# 4WD_V1_0.net
KiCad netlist of a schematic drawn in Altium Designer
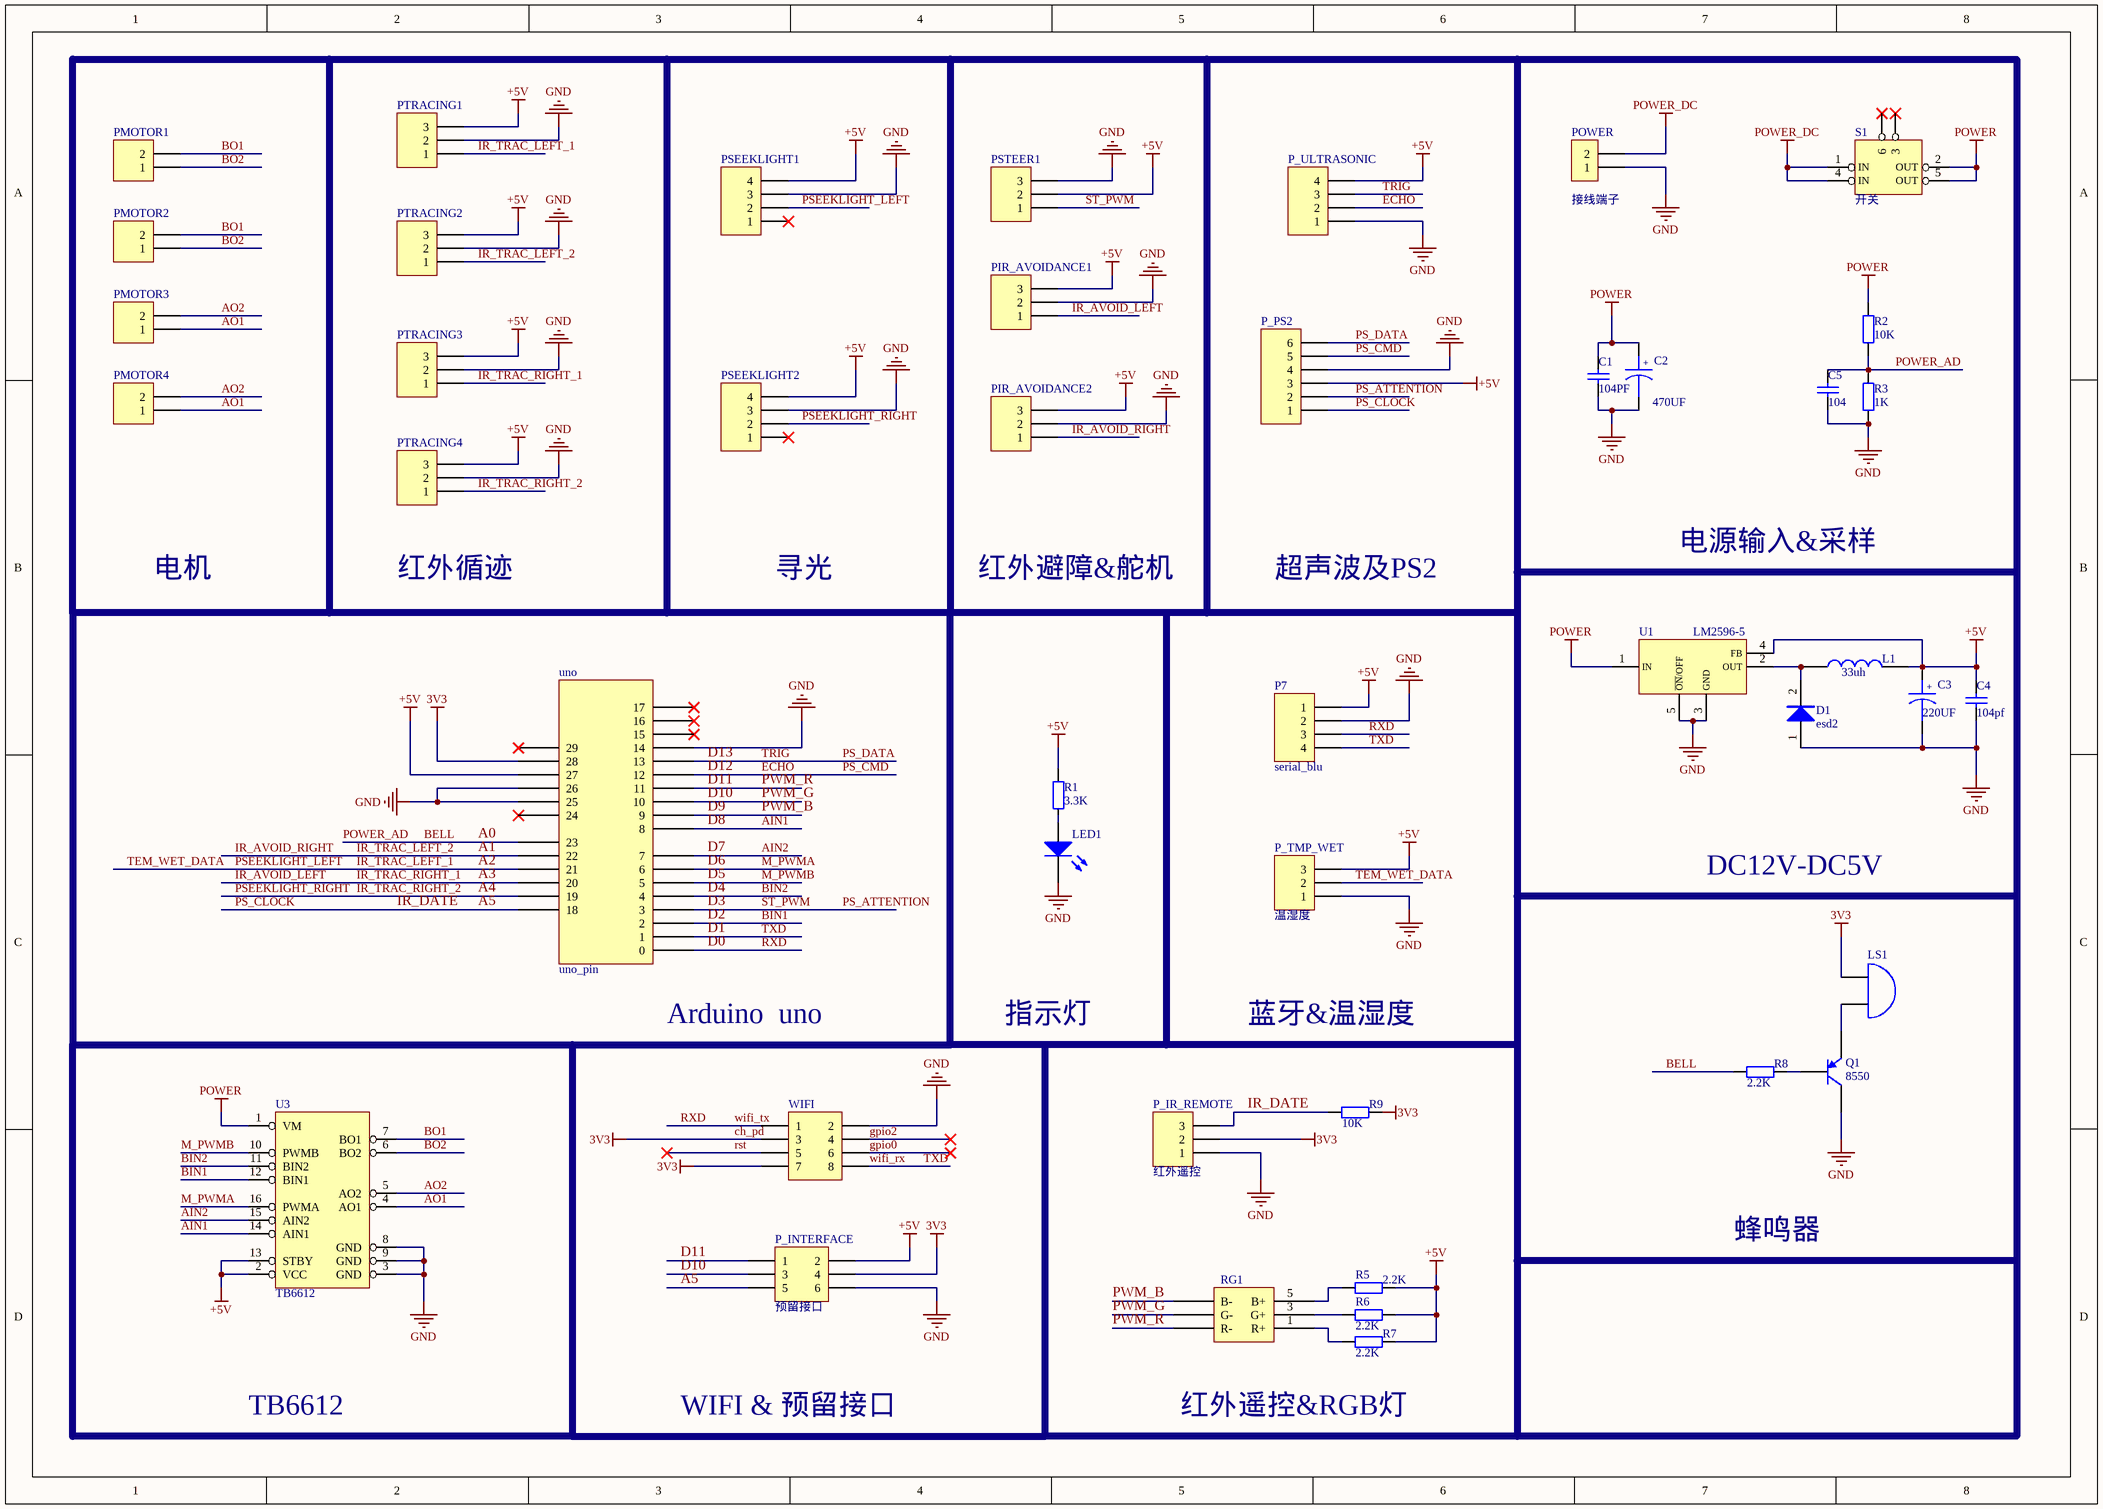
[diagram p0: 4WD_V1.0.SchDoc]

(export (version "E")
  (design (tool "Eeschema 10.0.6"))
  (components
    (comp (ref "C1")
      (value "Cap")
      (footprint "C 0603_L")
      (description "Capacitor")
      (fields (field (name "ALTIUM_UNNAMED_1") "104PF") (field (name "PUBLISHER") "Altium Limited"))
      (libsource (lib "balanceDriver") (part "Cap"))
    )
    (comp (ref "C2")
      (value "CAP4 电解电容")
      (footprint "CAP6.3")
      (description "Capacitor")
      (fields (field (name "ALTIUM_UNNAMED_1") "470UF"))
      (libsource (lib "double_wheel_ctrl") (part "CAP4 电解电容"))
    )
    (comp (ref "C3")
      (value "CAP4 电解电容")
      (footprint "CAP6.3")
      (description "Capacitor")
      (fields (field (name "ALTIUM_UNNAMED_1") "220UF"))
      (libsource (lib "double_wheel_ctrl") (part "CAP4 电解电容"))
    )
    (comp (ref "C4")
      (value "Cap")
      (footprint "C 0603_L")
      (description "Capacitor")
      (fields (field (name "ALTIUM_UNNAMED_1") "104pf") (field (name "PUBLISHER") "Altium Limited"))
      (libsource (lib "balanceDriver") (part "Cap"))
    )
    (comp (ref "C5")
      (value "104")
      (footprint "C 0603_L")
      (description "Capacitor")
      (fields (field (name "Comment") "Cap") (field (name "PUBLISHER") "Altium Limited"))
      (libsource (lib "Miscellaneous Devices") (part "Cap"))
    )
    (comp (ref "D1") (value "esd2") (footprint "SMA") (libsource (lib "double_wheel_ctrl") (part "DIODE2")))
    (comp (ref "L1")
      (value "INDUCTOR 0")
      (footprint "CDRH74")
      (fields (field (name "ALTIUM_UNNAMED_1") "33uh"))
      (libsource (lib "balanceDriver") (part "INDUCTOR 0"))
    )
    (comp (ref "LED1")
      (value "LED3")
      (footprint "LED 0603Y")
      (description "Typical RED, GREEN, YELLOW, AMBER GaAs LED")
      (fields (field (name "PUBLISHER") "Altium Limited"))
      (libsource (lib "Miscellaneous Devices") (part "LED2"))
    )
    (comp (ref "LS1")
      (value "Bell")
      (footprint "BEEP 5x9x5.5")
      (description "Electrical Bell")
      (fields (field (name "PUBLISHER") "Altium Limited"))
      (libsource (lib "Miscellaneous Devices") (part "Bell"))
    )
    (comp (ref "P7")
      (value "serial_blu")
      (footprint "HDR2.54-M-LI-4P")
      (description "Header, 4-Pin")
      (fields (field (name "PUBLISHER") "Altium Limited"))
      (libsource (lib "Miscellaneous Connectors") (part "Header 4"))
    )
    (comp (ref "PIR_AVOIDANCE1")
      (value "Header 3")
      (footprint "XH2.54-WI-3P")
      (description "Header, 3-Pin")
      (fields (field (name "PUBLISHER") "Altium Limited"))
      (libsource (lib "Miscellaneous Connectors") (part "Header 3"))
    )
    (comp (ref "PIR_AVOIDANCE2")
      (value "Header 3")
      (footprint "XH2.54-WI-3P")
      (description "Header, 3-Pin")
      (fields (field (name "PUBLISHER") "Altium Limited"))
      (libsource (lib "Miscellaneous Connectors") (part "Header 3"))
    )
    (comp (ref "PMOTOR1")
      (value "Header 2")
      (footprint "XH2.54-WI-2P")
      (description "Header, 2-Pin")
      (fields (field (name "PUBLISHER") "Altium Limited"))
      (libsource (lib "Miscellaneous Connectors") (part "Header 2"))
    )
    (comp (ref "PMOTOR2")
      (value "Header 2")
      (footprint "XH2.54-WI-2P")
      (description "Header, 2-Pin")
      (fields (field (name "PUBLISHER") "Altium Limited"))
      (libsource (lib "Miscellaneous Connectors") (part "Header 2"))
    )
    (comp (ref "PMOTOR3")
      (value "Header 2")
      (footprint "XH2.54-WI-2P")
      (description "Header, 2-Pin")
      (fields (field (name "PUBLISHER") "Altium Limited"))
      (libsource (lib "Miscellaneous Connectors") (part "Header 2"))
    )
    (comp (ref "PMOTOR4")
      (value "Header 2")
      (footprint "XH2.54-WI-2P")
      (description "Header, 2-Pin")
      (fields (field (name "PUBLISHER") "Altium Limited"))
      (libsource (lib "Miscellaneous Connectors") (part "Header 2"))
    )
    (comp (ref "POWER")
      (value "接线端子")
      (footprint "XH2.54-WI-2P")
      (libsource (lib "double_wheel_ctrl") (part "PIN2"))
    )
    (comp (ref "PSEEKLIGHT1")
      (value "Header 4")
      (footprint "XH2.54-WI-4P")
      (description "Header, 4-Pin")
      (fields (field (name "PUBLISHER") "Altium Limited"))
      (libsource (lib "") (part "Header 4_1"))
    )
    (comp (ref "PSEEKLIGHT2")
      (value "Header 4")
      (footprint "XH2.54-WI-4P")
      (description "Header, 4-Pin")
      (fields (field (name "PUBLISHER") "Altium Limited"))
      (libsource (lib "") (part "Header 4_1"))
    )
    (comp (ref "PSTEER1")
      (value "Header 3")
      (footprint "HDR2.54-WI-3P")
      (description "Header, 3-Pin")
      (fields (field (name "PUBLISHER") "Altium Limited"))
      (libsource (lib "Miscellaneous Connectors") (part "Header 3"))
    )
    (comp (ref "PTRACING1")
      (value "Header 3")
      (footprint "XH2.54-WI-3P")
      (description "Header, 3-Pin")
      (fields (field (name "PUBLISHER") "Altium Limited"))
      (libsource (lib "Miscellaneous Connectors") (part "Header 3"))
    )
    (comp (ref "PTRACING2")
      (value "Header 3")
      (footprint "XH2.54-WI-3P")
      (description "Header, 3-Pin")
      (fields (field (name "PUBLISHER") "Altium Limited"))
      (libsource (lib "Miscellaneous Connectors") (part "Header 3"))
    )
    (comp (ref "PTRACING3")
      (value "Header 3")
      (footprint "XH2.54-WI-3P")
      (description "Header, 3-Pin")
      (fields (field (name "PUBLISHER") "Altium Limited"))
      (libsource (lib "Miscellaneous Connectors") (part "Header 3"))
    )
    (comp (ref "PTRACING4")
      (value "Header 3")
      (footprint "XH2.54-WI-3P")
      (description "Header, 3-Pin")
      (fields (field (name "PUBLISHER") "Altium Limited"))
      (libsource (lib "Miscellaneous Connectors") (part "Header 3"))
    )
    (comp (ref "P_INTERFACE")
      (value "预留接口")
      (footprint "HDR2.54-LI-2x3P")
      (description "Header, 3-Pin, Dual row")
      (fields (field (name "PUBLISHER") "Altium Limited"))
      (libsource (lib "Miscellaneous Connectors") (part "Header 3X2"))
    )
    (comp (ref "P_IR_REMOTE")
      (value "红外遥控")
      (footprint "HDR2.54-M-LI-3P")
      (description "Header, 3-Pin")
      (fields (field (name "PUBLISHER") "Altium Limited"))
      (libsource (lib "Miscellaneous Connectors") (part "Header 3"))
    )
    (comp (ref "P_PS2")
      (value "Header 6")
      (footprint "HDR2.54-LI-6P")
      (description "Header, 6-Pin")
      (fields (field (name "PUBLISHER") "Altium Limited"))
      (libsource (lib "Miscellaneous Connectors") (part "Header 6"))
    )
    (comp (ref "P_TMP_WET")
      (value "温湿度")
      (footprint "HDR2.54-M-LI-3P")
      (description "Header, 3-Pin")
      (fields (field (name "PUBLISHER") "Altium Limited"))
      (libsource (lib "Miscellaneous Connectors") (part "Header 3"))
    )
    (comp (ref "P_ULTRASONIC")
      (value "Header 4")
      (footprint "HDR2.54-WI-4P")
      (description "Header, 4-Pin")
      (fields (field (name "PUBLISHER") "Altium Limited"))
      (libsource (lib "") (part "Header 4_1"))
    )
    (comp (ref "Q1")
      (value "8550")
      (footprint "SOT23-3L")
      (description "PNP General Purpose Amplifier")
      (fields (field (name "PUBLISHER") "Altium Limited"))
      (libsource (lib "4WD_ARDUINO_PCB_QINHE") (part "2N3906"))
    )
    (comp (ref "R1")
      (value "3.3K")
      (footprint "R 0603_L")
      (description "Resistor")
      (fields (field (name "Comment") "Res2") (field (name "PUBLISHER") "Altium Limited"))
      (libsource (lib "Miscellaneous Devices") (part "Res2"))
    )
    (comp (ref "R2")
      (value "10K")
      (footprint "R 0603_L")
      (description "Resistor")
      (fields (field (name "Comment") "Res2") (field (name "PUBLISHER") "Altium Limited"))
      (libsource (lib "Miscellaneous Devices") (part "Res2"))
    )
    (comp (ref "R3")
      (value "1K")
      (footprint "R 0603_L")
      (description "Resistor")
      (fields (field (name "Comment") "Res2") (field (name "PUBLISHER") "Altium Limited"))
      (libsource (lib "Miscellaneous Devices") (part "Res2"))
    )
    (comp (ref "R5")
      (value "2.2K")
      (footprint "R 0603_L")
      (description "Resistor")
      (fields (field (name "Comment") "Res2") (field (name "PUBLISHER") "Altium Limited"))
      (libsource (lib "") (part "Res2_1"))
    )
    (comp (ref "R6")
      (value "2.2K")
      (footprint "R 0603_L")
      (description "Resistor")
      (fields (field (name "Comment") "Res2") (field (name "PUBLISHER") "Altium Limited"))
      (libsource (lib "") (part "Res2_1"))
    )
    (comp (ref "R7")
      (value "2.2K")
      (footprint "R 0603_L")
      (description "Resistor")
      (fields (field (name "Comment") "Res2") (field (name "PUBLISHER") "Altium Limited"))
      (libsource (lib "") (part "Res2_1"))
    )
    (comp (ref "R8")
      (value "2.2K")
      (footprint "R 0603_L")
      (description "Resistor")
      (fields (field (name "Comment") "Res2") (field (name "PUBLISHER") "Altium Limited"))
      (libsource (lib "") (part "Res2_1"))
    )
    (comp (ref "R9")
      (value "10K")
      (footprint "R 0603_L")
      (description "Resistor")
      (fields (field (name "Comment") "Res2") (field (name "PUBLISHER") "Altium Limited"))
      (libsource (lib "") (part "Res2_1"))
    )
    (comp (ref "RG1")
      (value "RGB_LED_6")
      (footprint "LED 5050")
      (libsource (lib "RGB_PCB") (part "RGB_LED_6"))
    )
    (comp (ref "S1")
      (value "开关")
      (footprint "SWITCH_SELFLOCKING")
      (libsource (lib "double_wheel_ctrl") (part "switch"))
    )
    (comp (ref "U1")
      (value "LM2596-5")
      (footprint "TO263-5A")
      (libsource (lib "balanceDriver") (part "LM2560-5"))
    )
    (comp (ref "U3")
      (value "TB6612")
      (footprint "TB6612")
      (libsource (lib "double_wheel_ctrl") (part "TB6612"))
    )
    (comp (ref "uno") (value "uno_pin") (footprint "UNO_PIN") (libsource (lib "driver") (part "uno_pin")))
    (comp (ref "WIFI")
      (value "Header 4X2")
      (footprint "wifi")
      (description "Header, 4-Pin, Dual row")
      (fields (field (name "PUBLISHER") "Altium Limited"))
      (libsource (lib "Miscellaneous Connectors") (part "Header 4X2"))
    )
  )
  (nets
    (net (code "1") (name "+5V") (class "Default")
      (node (ref "C3") (pin "1") (pinfunction "1_1") (pintype "passive"))
      (node (ref "C4") (pin "2") (pinfunction "2_2") (pintype "passive"))
      (node (ref "L1") (pin "2") (pinfunction "2_2") (pintype "passive"))
      (node (ref "P7") (pin "1") (pinfunction "1_1") (pintype "passive"))
      (node (ref "PIR_AVOIDANCE1") (pin "3") (pinfunction "3_3") (pintype "passive"))
      (node (ref "PIR_AVOIDANCE2") (pin "3") (pinfunction "3_3") (pintype "passive"))
      (node (ref "PSEEKLIGHT1") (pin "4") (pinfunction "4_4") (pintype "passive"))
      (node (ref "PSEEKLIGHT2") (pin "4") (pinfunction "4_4") (pintype "passive"))
      (node (ref "PSTEER1") (pin "2") (pinfunction "2_2") (pintype "passive"))
      (node (ref "PTRACING1") (pin "3") (pinfunction "3_3") (pintype "passive"))
      (node (ref "PTRACING2") (pin "3") (pinfunction "3_3") (pintype "passive"))
      (node (ref "PTRACING3") (pin "3") (pinfunction "3_3") (pintype "passive"))
      (node (ref "PTRACING4") (pin "3") (pinfunction "3_3") (pintype "passive"))
      (node (ref "P_INTERFACE") (pin "2") (pinfunction "2_2") (pintype "passive"))
      (node (ref "P_PS2") (pin "3") (pinfunction "3_3") (pintype "passive"))
      (node (ref "P_TMP_WET") (pin "3") (pinfunction "3_3") (pintype "passive"))
      (node (ref "P_ULTRASONIC") (pin "4") (pinfunction "4_4") (pintype "passive"))
      (node (ref "R1") (pin "1") (pinfunction "1_1") (pintype "passive"))
      (node (ref "R5") (pin "1") (pinfunction "1_1") (pintype "passive"))
      (node (ref "R6") (pin "1") (pinfunction "1_1") (pintype "passive"))
      (node (ref "R7") (pin "1") (pinfunction "1_1") (pintype "passive"))
      (node (ref "U1") (pin "4") (pinfunction "FB_4") (pintype "passive"))
      (node (ref "U3") (pin "13") (pinfunction "STBY_13") (pintype "passive"))
      (node (ref "U3") (pin "2") (pinfunction "VCC_2") (pintype "passive"))
      (node (ref "uno") (pin "27") (pinfunction "27_27") (pintype "passive"))
    )
    (net (code "2") (name "/A0") (class "Default")
      (node (ref "C5") (pin "1") (pinfunction "1_1") (pintype "passive"))
      (node (ref "R2") (pin "2") (pinfunction "2_2") (pintype "passive"))
      (node (ref "R3") (pin "1") (pinfunction "1_1") (pintype "passive"))
      (node (ref "R8") (pin "2") (pinfunction "2_2") (pintype "passive"))
      (node (ref "uno") (pin "23") (pinfunction "23_23") (pintype "passive"))
    )
    (net (code "3") (name "/A1") (class "Default")
      (node (ref "PIR_AVOIDANCE2") (pin "1") (pinfunction "1_1") (pintype "passive"))
      (node (ref "PTRACING2") (pin "1") (pinfunction "1_1") (pintype "passive"))
      (node (ref "uno") (pin "22") (pinfunction "22_22") (pintype "passive"))
    )
    (net (code "4") (name "/A2") (class "Default")
      (node (ref "PSEEKLIGHT1") (pin "2") (pinfunction "2_2") (pintype "passive"))
      (node (ref "PTRACING1") (pin "1") (pinfunction "1_1") (pintype "passive"))
      (node (ref "P_TMP_WET") (pin "2") (pinfunction "2_2") (pintype "passive"))
      (node (ref "uno") (pin "21") (pinfunction "21_21") (pintype "passive"))
    )
    (net (code "5") (name "/A3") (class "Default")
      (node (ref "PIR_AVOIDANCE1") (pin "1") (pinfunction "1_1") (pintype "passive"))
      (node (ref "PTRACING3") (pin "1") (pinfunction "1_1") (pintype "passive"))
      (node (ref "uno") (pin "20") (pinfunction "20_20") (pintype "passive"))
    )
    (net (code "6") (name "/A4") (class "Default")
      (node (ref "PSEEKLIGHT2") (pin "2") (pinfunction "2_2") (pintype "passive"))
      (node (ref "PTRACING4") (pin "1") (pinfunction "1_1") (pintype "passive"))
      (node (ref "uno") (pin "19") (pinfunction "19_19") (pintype "passive"))
    )
    (net (code "7") (name "/A5") (class "Default")
      (node (ref "P_INTERFACE") (pin "5") (pinfunction "5_5") (pintype "passive"))
      (node (ref "P_IR_REMOTE") (pin "3") (pinfunction "3_3") (pintype "passive"))
      (node (ref "P_PS2") (pin "1") (pinfunction "1_1") (pintype "passive"))
      (node (ref "R9") (pin "2") (pinfunction "2_2") (pintype "passive"))
      (node (ref "uno") (pin "18") (pinfunction "18_18") (pintype "passive"))
    )
    (net (code "8") (name "/AIN1") (class "Default")
      (node (ref "U3") (pin "14") (pinfunction "AIN1_14") (pintype "passive"))
      (node (ref "uno") (pin "8") (pinfunction "8_8") (pintype "passive"))
    )
    (net (code "9") (name "/AIN2") (class "Default")
      (node (ref "U3") (pin "15") (pinfunction "AIN2_15") (pintype "passive"))
      (node (ref "uno") (pin "7") (pinfunction "7_7") (pintype "passive"))
    )
    (net (code "10") (name "/AO1") (class "Default")
      (node (ref "PMOTOR3") (pin "1") (pinfunction "1_1") (pintype "passive"))
      (node (ref "PMOTOR4") (pin "1") (pinfunction "1_1") (pintype "passive"))
      (node (ref "U3") (pin "4") (pinfunction "AO1_4") (pintype "passive"))
    )
    (net (code "11") (name "/AO2") (class "Default")
      (node (ref "PMOTOR3") (pin "2") (pinfunction "2_2") (pintype "passive"))
      (node (ref "PMOTOR4") (pin "2") (pinfunction "2_2") (pintype "passive"))
      (node (ref "U3") (pin "5") (pinfunction "AO2_5") (pintype "passive"))
    )
    (net (code "12") (name "/BIN1") (class "Default")
      (node (ref "U3") (pin "12") (pinfunction "BIN1_12") (pintype "passive"))
      (node (ref "uno") (pin "2") (pinfunction "2_2") (pintype "passive"))
    )
    (net (code "13") (name "/BIN2") (class "Default")
      (node (ref "U3") (pin "11") (pinfunction "BIN2_11") (pintype "passive"))
      (node (ref "uno") (pin "4") (pinfunction "4_4") (pintype "passive"))
    )
    (net (code "14") (name "/BO1") (class "Default")
      (node (ref "PMOTOR1") (pin "2") (pinfunction "2_2") (pintype "passive"))
      (node (ref "PMOTOR2") (pin "2") (pinfunction "2_2") (pintype "passive"))
      (node (ref "U3") (pin "7") (pinfunction "BO1_7") (pintype "passive"))
    )
    (net (code "15") (name "/BO2") (class "Default")
      (node (ref "PMOTOR1") (pin "1") (pinfunction "1_1") (pintype "passive"))
      (node (ref "PMOTOR2") (pin "1") (pinfunction "1_1") (pintype "passive"))
      (node (ref "U3") (pin "6") (pinfunction "BO2_6") (pintype "passive"))
    )
    (net (code "16") (name "/D0") (class "Default")
      (node (ref "P7") (pin "3") (pinfunction "3_3") (pintype "passive"))
      (node (ref "WIFI") (pin "1") (pinfunction "1_1") (pintype "passive"))
      (node (ref "uno") (pin "0") (pinfunction "0_0") (pintype "passive"))
    )
    (net (code "17") (name "/D1") (class "Default")
      (node (ref "P7") (pin "4") (pinfunction "4_4") (pintype "passive"))
      (node (ref "WIFI") (pin "8") (pinfunction "8_8") (pintype "passive"))
      (node (ref "uno") (pin "1") (pinfunction "1_1") (pintype "passive"))
    )
    (net (code "18") (name "/D3") (class "Default")
      (node (ref "PSTEER1") (pin "1") (pinfunction "1_1") (pintype "passive"))
      (node (ref "P_PS2") (pin "2") (pinfunction "2_2") (pintype "passive"))
      (node (ref "uno") (pin "3") (pinfunction "3_3") (pintype "passive"))
    )
    (net (code "19") (name "/D5") (class "Default")
      (node (ref "U3") (pin "10") (pinfunction "PWMB_10") (pintype "passive"))
      (node (ref "uno") (pin "5") (pinfunction "5_5") (pintype "passive"))
    )
    (net (code "20") (name "/D6") (class "Default")
      (node (ref "U3") (pin "16") (pinfunction "PWMA_16") (pintype "passive"))
      (node (ref "uno") (pin "6") (pinfunction "6_6") (pintype "passive"))
    )
    (net (code "21") (name "/D9") (class "Default")
      (node (ref "RG1") (pin "6") (pinfunction "B-_6") (pintype "power_in"))
      (node (ref "uno") (pin "9") (pinfunction "9_9") (pintype "passive"))
    )
    (net (code "22") (name "/D10") (class "Default")
      (node (ref "P_INTERFACE") (pin "3") (pinfunction "3_3") (pintype "passive"))
      (node (ref "RG1") (pin "4") (pinfunction "G-_4") (pintype "power_in"))
      (node (ref "uno") (pin "10") (pinfunction "10_10") (pintype "passive"))
    )
    (net (code "23") (name "/D11") (class "Default")
      (node (ref "P_INTERFACE") (pin "1") (pinfunction "1_1") (pintype "passive"))
      (node (ref "RG1") (pin "2") (pinfunction "R-_2") (pintype "power_in"))
      (node (ref "uno") (pin "11") (pinfunction "11_11") (pintype "passive"))
    )
    (net (code "24") (name "/D12") (class "Default")
      (node (ref "P_PS2") (pin "5") (pinfunction "5_5") (pintype "passive"))
      (node (ref "P_ULTRASONIC") (pin "2") (pinfunction "2_2") (pintype "passive"))
      (node (ref "uno") (pin "12") (pinfunction "12_12") (pintype "passive"))
    )
    (net (code "25") (name "/D13") (class "Default")
      (node (ref "P_PS2") (pin "6") (pinfunction "6_6") (pintype "passive"))
      (node (ref "P_ULTRASONIC") (pin "3") (pinfunction "3_3") (pintype "passive"))
      (node (ref "uno") (pin "13") (pinfunction "13_13") (pintype "passive"))
    )
    (net (code "26") (name "/gpio0") (class "Default")
      (node (ref "WIFI") (pin "6") (pinfunction "6_6") (pintype "passive+no_connect"))
    )
    (net (code "27") (name "/gpio2") (class "Default")
      (node (ref "WIFI") (pin "4") (pinfunction "4_4") (pintype "passive+no_connect"))
    )
    (net (code "28") (name "/rst") (class "Default")
      (node (ref "WIFI") (pin "5") (pinfunction "5_5") (pintype "passive+no_connect"))
    )
    (net (code "29") (name "3V3") (class "Default")
      (node (ref "LS1") (pin "1") (pinfunction "A_1") (pintype "passive"))
      (node (ref "P_INTERFACE") (pin "4") (pinfunction "4_4") (pintype "passive"))
      (node (ref "P_IR_REMOTE") (pin "2") (pinfunction "2_2") (pintype "passive"))
      (node (ref "R9") (pin "1") (pinfunction "1_1") (pintype "passive"))
      (node (ref "WIFI") (pin "3") (pinfunction "3_3") (pintype "passive"))
      (node (ref "WIFI") (pin "7") (pinfunction "7_7") (pintype "passive"))
      (node (ref "uno") (pin "28") (pinfunction "28_28") (pintype "passive"))
    )
    (net (code "30") (name "GND") (class "Default")
      (node (ref "C1") (pin "1") (pinfunction "1_1") (pintype "passive"))
      (node (ref "C2") (pin "2") (pinfunction "2_2") (pintype "passive"))
      (node (ref "C3") (pin "2") (pinfunction "2_2") (pintype "passive"))
      (node (ref "C4") (pin "1") (pinfunction "1_1") (pintype "passive"))
      (node (ref "C5") (pin "2") (pinfunction "2_2") (pintype "passive"))
      (node (ref "D1") (pin "1") (pinfunction "1_1") (pintype "passive"))
      (node (ref "LED1") (pin "2") (pinfunction "K_2") (pintype "passive"))
      (node (ref "P7") (pin "2") (pinfunction "2_2") (pintype "passive"))
      (node (ref "PIR_AVOIDANCE1") (pin "2") (pinfunction "2_2") (pintype "passive"))
      (node (ref "PIR_AVOIDANCE2") (pin "2") (pinfunction "2_2") (pintype "passive"))
      (node (ref "POWER") (pin "1") (pinfunction "1_1") (pintype "passive"))
      (node (ref "PSEEKLIGHT1") (pin "3") (pinfunction "3_3") (pintype "passive"))
      (node (ref "PSEEKLIGHT2") (pin "3") (pinfunction "3_3") (pintype "passive"))
      (node (ref "PSTEER1") (pin "3") (pinfunction "3_3") (pintype "passive"))
      (node (ref "PTRACING1") (pin "2") (pinfunction "2_2") (pintype "passive"))
      (node (ref "PTRACING2") (pin "2") (pinfunction "2_2") (pintype "passive"))
      (node (ref "PTRACING3") (pin "2") (pinfunction "2_2") (pintype "passive"))
      (node (ref "PTRACING4") (pin "2") (pinfunction "2_2") (pintype "passive"))
      (node (ref "P_INTERFACE") (pin "6") (pinfunction "6_6") (pintype "passive"))
      (node (ref "P_IR_REMOTE") (pin "1") (pinfunction "1_1") (pintype "passive"))
      (node (ref "P_PS2") (pin "4") (pinfunction "4_4") (pintype "passive"))
      (node (ref "P_TMP_WET") (pin "1") (pinfunction "1_1") (pintype "passive"))
      (node (ref "P_ULTRASONIC") (pin "1") (pinfunction "1_1") (pintype "passive"))
      (node (ref "Q1") (pin "3") (pinfunction "C_3") (pintype "passive"))
      (node (ref "R3") (pin "2") (pinfunction "2_2") (pintype "passive"))
      (node (ref "U1") (pin "3") (pinfunction "GND_3") (pintype "passive"))
      (node (ref "U1") (pin "5") (pinfunction "~{ON}/OFF_5") (pintype "passive"))
      (node (ref "U3") (pin "3") (pinfunction "GND_3") (pintype "passive"))
      (node (ref "U3") (pin "8") (pinfunction "GND_8") (pintype "passive"))
      (node (ref "U3") (pin "9") (pinfunction "GND_9") (pintype "passive"))
      (node (ref "WIFI") (pin "2") (pinfunction "2_2") (pintype "passive"))
      (node (ref "uno") (pin "14") (pinfunction "14_14") (pintype "passive"))
      (node (ref "uno") (pin "25") (pinfunction "25_25") (pintype "passive"))
      (node (ref "uno") (pin "26") (pinfunction "26_26") (pintype "passive"))
    )
    (net (code "31") (name "Net-(LED1-A)") (class "Default")
      (node (ref "LED1") (pin "1") (pinfunction "A_1") (pintype "passive"))
      (node (ref "R1") (pin "2") (pinfunction "2_2") (pintype "passive"))
    )
    (net (code "32") (name "Net-(LS1-B)") (class "Default")
      (node (ref "LS1") (pin "2") (pinfunction "B_2") (pintype "passive"))
      (node (ref "Q1") (pin "2") (pinfunction "E_2") (pintype "passive"))
    )
    (net (code "33") (name "Net-(Q1-B)") (class "Default")
      (node (ref "Q1") (pin "1") (pinfunction "B_1") (pintype "passive"))
      (node (ref "R8") (pin "1") (pinfunction "1_1") (pintype "passive"))
    )
    (net (code "34") (name "Net-(RG1-B+)") (class "Default")
      (node (ref "R5") (pin "2") (pinfunction "2_2") (pintype "passive"))
      (node (ref "RG1") (pin "5") (pinfunction "B+_5") (pintype "power_in"))
    )
    (net (code "35") (name "Net-(RG1-G+)") (class "Default")
      (node (ref "R6") (pin "2") (pinfunction "2_2") (pintype "passive"))
      (node (ref "RG1") (pin "3") (pinfunction "G+_3") (pintype "power_in"))
    )
    (net (code "36") (name "Net-(RG1-R+)") (class "Default")
      (node (ref "R7") (pin "2") (pinfunction "2_2") (pintype "passive"))
      (node (ref "RG1") (pin "1") (pinfunction "R+_1") (pintype "power_in"))
    )
    (net (code "37") (name "Net-(U1-OUT)") (class "Default")
      (node (ref "D1") (pin "2") (pinfunction "2_2") (pintype "passive"))
      (node (ref "L1") (pin "1") (pinfunction "1_1") (pintype "passive"))
      (node (ref "U1") (pin "2") (pinfunction "OUT_2") (pintype "passive"))
    )
    (net (code "38") (name "POWER") (class "Default")
      (node (ref "C1") (pin "2") (pinfunction "2_2") (pintype "passive"))
      (node (ref "C2") (pin "1") (pinfunction "1_1") (pintype "passive"))
      (node (ref "R2") (pin "1") (pinfunction "1_1") (pintype "passive"))
      (node (ref "S1") (pin "2") (pinfunction "OUT_2") (pintype "passive"))
      (node (ref "S1") (pin "5") (pinfunction "OUT_5") (pintype "passive"))
      (node (ref "U1") (pin "1") (pinfunction "IN_1") (pintype "passive"))
      (node (ref "U3") (pin "1") (pinfunction "VM_1") (pintype "passive"))
    )
    (net (code "39") (name "POWER_DC") (class "Default")
      (node (ref "POWER") (pin "2") (pinfunction "2_2") (pintype "passive"))
      (node (ref "S1") (pin "1") (pinfunction "IN_1") (pintype "passive"))
      (node (ref "S1") (pin "4") (pinfunction "IN_4") (pintype "passive"))
    )
    (net (code "40") (name "unconnected-(PSEEKLIGHT1-Pad1)") (class "Default")
      (node (ref "PSEEKLIGHT1") (pin "1") (pinfunction "1_1") (pintype "passive+no_connect"))
    )
    (net (code "41") (name "unconnected-(PSEEKLIGHT2-Pad1)") (class "Default")
      (node (ref "PSEEKLIGHT2") (pin "1") (pinfunction "1_1") (pintype "passive+no_connect"))
    )
    (net (code "42") (name "unconnected-(S1-Pad3)") (class "Default")
      (node (ref "S1") (pin "3") (pinfunction "3_3") (pintype "passive+no_connect"))
    )
    (net (code "43") (name "unconnected-(S1-Pad6)") (class "Default")
      (node (ref "S1") (pin "6") (pinfunction "6_6") (pintype "passive+no_connect"))
    )
    (net (code "44") (name "unconnected-(uno-Pad15)") (class "Default")
      (node (ref "uno") (pin "15") (pinfunction "15_15") (pintype "passive+no_connect"))
    )
    (net (code "45") (name "unconnected-(uno-Pad16)") (class "Default")
      (node (ref "uno") (pin "16") (pinfunction "16_16") (pintype "passive+no_connect"))
    )
    (net (code "46") (name "unconnected-(uno-Pad17)") (class "Default")
      (node (ref "uno") (pin "17") (pinfunction "17_17") (pintype "passive+no_connect"))
    )
    (net (code "47") (name "unconnected-(uno-Pad24)") (class "Default")
      (node (ref "uno") (pin "24") (pinfunction "24_24") (pintype "passive+no_connect"))
    )
    (net (code "48") (name "unconnected-(uno-Pad29)") (class "Default")
      (node (ref "uno") (pin "29") (pinfunction "29_29") (pintype "passive+no_connect"))
    )
  )
)
